# 04-OUTPUT.net
KiCad netlist of a schematic drawn in Altium Designer
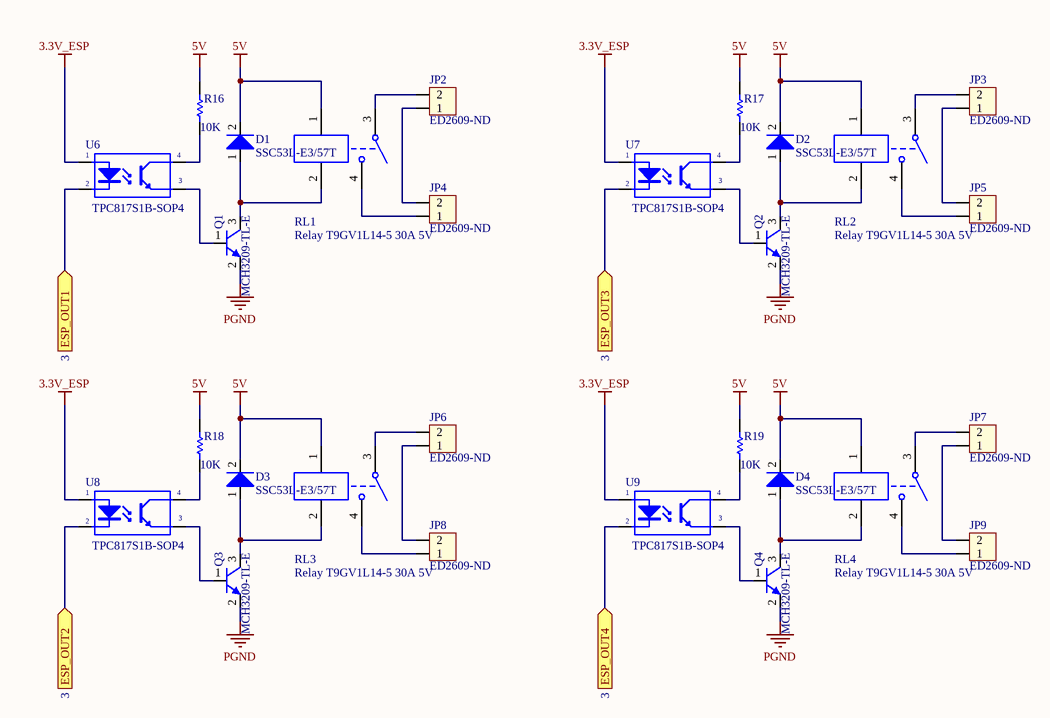
[diagram p0: 04-OUTPUT.SchDoc]

(export (version "E")
  (design (tool "Eeschema 10.0.6"))
  (components
    (comp (ref "D1")
      (value "SSC53L-E3/57T")
      (footprint "SSC53L-E3/57T")
      (description "DIODE SCHOTTKY 30V 5A DO214AB")
      (libsource (lib "lpson") (part "10A10"))
    )
    (comp (ref "D2")
      (value "SSC53L-E3/57T")
      (footprint "SSC53L-E3/57T")
      (description "DIODE SCHOTTKY 30V 5A DO214AB")
      (libsource (lib "lpson") (part "10A10"))
    )
    (comp (ref "D3")
      (value "SSC53L-E3/57T")
      (footprint "SSC53L-E3/57T")
      (description "DIODE SCHOTTKY 30V 5A DO214AB")
      (libsource (lib "lpson") (part "10A10"))
    )
    (comp (ref "D4")
      (value "SSC53L-E3/57T")
      (footprint "SSC53L-E3/57T")
      (description "DIODE SCHOTTKY 30V 5A DO214AB")
      (libsource (lib "lpson") (part "10A10"))
    )
    (comp (ref "JP2")
      (value "ED2609-ND")
      (footprint "DOMINO_OSTTC_2P")
      (description "2 Position Wire to Board Terminal Block Horizontal with Board 0.200\" (5.08mm) Through Hole")
      (libsource (lib "lpson") (part "Con2"))
    )
    (comp (ref "JP3")
      (value "ED2609-ND")
      (footprint "DOMINO_OSTTC_2P")
      (description "2 Position Wire to Board Terminal Block Horizontal with Board 0.200\" (5.08mm) Through Hole")
      (libsource (lib "lpson") (part "Con2"))
    )
    (comp (ref "JP4")
      (value "ED2609-ND")
      (footprint "DOMINO_OSTTC_2P")
      (description "2 Position Wire to Board Terminal Block Horizontal with Board 0.200\" (5.08mm) Through Hole")
      (libsource (lib "lpson") (part "Con2"))
    )
    (comp (ref "JP5")
      (value "ED2609-ND")
      (footprint "DOMINO_OSTTC_2P")
      (description "2 Position Wire to Board Terminal Block Horizontal with Board 0.200\" (5.08mm) Through Hole")
      (libsource (lib "lpson") (part "Con2"))
    )
    (comp (ref "JP6")
      (value "ED2609-ND")
      (footprint "DOMINO_OSTTC_2P")
      (description "2 Position Wire to Board Terminal Block Horizontal with Board 0.200\" (5.08mm) Through Hole")
      (libsource (lib "lpson") (part "Con2"))
    )
    (comp (ref "JP7")
      (value "ED2609-ND")
      (footprint "DOMINO_OSTTC_2P")
      (description "2 Position Wire to Board Terminal Block Horizontal with Board 0.200\" (5.08mm) Through Hole")
      (libsource (lib "lpson") (part "Con2"))
    )
    (comp (ref "JP8")
      (value "ED2609-ND")
      (footprint "DOMINO_OSTTC_2P")
      (description "2 Position Wire to Board Terminal Block Horizontal with Board 0.200\" (5.08mm) Through Hole")
      (libsource (lib "lpson") (part "Con2"))
    )
    (comp (ref "JP9")
      (value "ED2609-ND")
      (footprint "DOMINO_OSTTC_2P")
      (description "2 Position Wire to Board Terminal Block Horizontal with Board 0.200\" (5.08mm) Through Hole")
      (libsource (lib "lpson") (part "Con2"))
    )
    (comp (ref "Q1")
      (value "MCH3209-TL-E")
      (footprint "MCH3209-TL-E  SOT-323")
      (description "Bipolar (BJT) Transistor NPN 30V 3A 450MHz 800mW Surface Mount 3-MCPH")
      (libsource (lib "lpson") (part "2SC1815"))
    )
    (comp (ref "Q2")
      (value "MCH3209-TL-E")
      (footprint "MCH3209-TL-E  SOT-323")
      (description "Bipolar (BJT) Transistor NPN 30V 3A 450MHz 800mW Surface Mount 3-MCPH")
      (libsource (lib "lpson") (part "2SC1815"))
    )
    (comp (ref "Q3")
      (value "MCH3209-TL-E")
      (footprint "MCH3209-TL-E  SOT-323")
      (description "Bipolar (BJT) Transistor NPN 30V 3A 450MHz 800mW Surface Mount 3-MCPH")
      (libsource (lib "lpson") (part "2SC1815"))
    )
    (comp (ref "Q4")
      (value "MCH3209-TL-E")
      (footprint "MCH3209-TL-E  SOT-323")
      (description "Bipolar (BJT) Transistor NPN 30V 3A 450MHz 800mW Surface Mount 3-MCPH")
      (libsource (lib "lpson") (part "2SC1815"))
    )
    (comp (ref "R16")
      (value "10K")
      (footprint "Res 0805 SMD")
      (description "RES SMD 249K OHM 1% 1/10W 0805")
      (fields
        (field (name "MANUFACTURER") "Yageo")
        (field (name "MANUFACTURER PART NUMBER") "RC0603FR-07249KL")
      )
      (libsource (lib "GSHT_181013") (part "249K/R0805/1%"))
    )
    (comp (ref "R17")
      (value "10K")
      (footprint "Res 0805 SMD")
      (description "RES SMD 249K OHM 1% 1/10W 0805")
      (fields
        (field (name "MANUFACTURER") "Yageo")
        (field (name "MANUFACTURER PART NUMBER") "RC0603FR-07249KL")
      )
      (libsource (lib "GSHT_181013") (part "249K/R0805/1%"))
    )
    (comp (ref "R18")
      (value "10K")
      (footprint "Res 0805 SMD")
      (description "RES SMD 249K OHM 1% 1/10W 0805")
      (fields
        (field (name "MANUFACTURER") "Yageo")
        (field (name "MANUFACTURER PART NUMBER") "RC0603FR-07249KL")
      )
      (libsource (lib "GSHT_181013") (part "249K/R0805/1%"))
    )
    (comp (ref "R19")
      (value "10K")
      (footprint "Res 0805 SMD")
      (description "RES SMD 249K OHM 1% 1/10W 0805")
      (fields
        (field (name "MANUFACTURER") "Yageo")
        (field (name "MANUFACTURER PART NUMBER") "RC0603FR-07249KL")
      )
      (libsource (lib "GSHT_181013") (part "249K/R0805/1%"))
    )
    (comp (ref "RL1")
      (value "Relay T9GV1L14-5 30A 5V")
      (footprint "Relay T9GV1L14-5 30A 5V")
      (description "General Purpose Relay SPST-NO (1 Form A) 5VDC Coil Through Hole")
      (libsource (lib "PCB_ESP32_RFID") (part "Relay T9GV1L14-5 30A 5V"))
    )
    (comp (ref "RL2")
      (value "Relay T9GV1L14-5 30A 5V")
      (footprint "Relay T9GV1L14-5 30A 5V")
      (description "General Purpose Relay SPST-NO (1 Form A) 5VDC Coil Through Hole")
      (libsource (lib "PCB_ESP32_RFID") (part "Relay T9GV1L14-5 30A 5V"))
    )
    (comp (ref "RL3")
      (value "Relay T9GV1L14-5 30A 5V")
      (footprint "Relay T9GV1L14-5 30A 5V")
      (description "General Purpose Relay SPST-NO (1 Form A) 5VDC Coil Through Hole")
      (libsource (lib "PCB_ESP32_RFID") (part "Relay T9GV1L14-5 30A 5V"))
    )
    (comp (ref "RL4")
      (value "Relay T9GV1L14-5 30A 5V")
      (footprint "Relay T9GV1L14-5 30A 5V")
      (description "General Purpose Relay SPST-NO (1 Form A) 5VDC Coil Through Hole")
      (libsource (lib "PCB_ESP32_RFID") (part "Relay T9GV1L14-5 30A 5V"))
    )
    (comp (ref "U6")
      (value "TPC817S1B-SOP4")
      (footprint "TPC817-4SOP")
      (description "Optoisolator Transistor Output 5000Vrms 1 Channel 4-SOP")
      (libsource (lib "lpson") (part "PC817"))
    )
    (comp (ref "U7")
      (value "TPC817S1B-SOP4")
      (footprint "TPC817-4SOP")
      (description "Optoisolator Transistor Output 5000Vrms 1 Channel 4-SOP")
      (libsource (lib "lpson") (part "PC817"))
    )
    (comp (ref "U8")
      (value "TPC817S1B-SOP4")
      (footprint "TPC817-4SOP")
      (description "Optoisolator Transistor Output 5000Vrms 1 Channel 4-SOP")
      (libsource (lib "lpson") (part "PC817"))
    )
    (comp (ref "U9")
      (value "TPC817S1B-SOP4")
      (footprint "TPC817-4SOP")
      (description "Optoisolator Transistor Output 5000Vrms 1 Channel 4-SOP")
      (libsource (lib "lpson") (part "PC817"))
    )
  )
  (nets
    (net (code "1") (name "/ESP_OUT1") (class "Default")
      (node (ref "U6") (pin "2") (pinfunction "K_2") (pintype "passive"))
    )
    (net (code "2") (name "/ESP_OUT2") (class "Default")
      (node (ref "U8") (pin "2") (pinfunction "K_2") (pintype "passive"))
    )
    (net (code "3") (name "/ESP_OUT3") (class "Default")
      (node (ref "U7") (pin "2") (pinfunction "K_2") (pintype "passive"))
    )
    (net (code "4") (name "/ESP_OUT4") (class "Default")
      (node (ref "U9") (pin "2") (pinfunction "K_2") (pintype "passive"))
    )
    (net (code "5") (name "3.3V_ESP") (class "Default")
      (node (ref "U6") (pin "1") (pinfunction "A_1") (pintype "passive"))
      (node (ref "U7") (pin "1") (pinfunction "A_1") (pintype "passive"))
      (node (ref "U8") (pin "1") (pinfunction "A_1") (pintype "passive"))
      (node (ref "U9") (pin "1") (pinfunction "A_1") (pintype "passive"))
    )
    (net (code "6") (name "5V") (class "Default")
      (node (ref "D1") (pin "2") (pinfunction "K_2") (pintype "passive"))
      (node (ref "D2") (pin "2") (pinfunction "K_2") (pintype "passive"))
      (node (ref "D3") (pin "2") (pinfunction "K_2") (pintype "passive"))
      (node (ref "D4") (pin "2") (pinfunction "K_2") (pintype "passive"))
      (node (ref "R16") (pin "2") (pinfunction "2_2") (pintype "passive"))
      (node (ref "R17") (pin "2") (pinfunction "2_2") (pintype "passive"))
      (node (ref "R18") (pin "2") (pinfunction "2_2") (pintype "passive"))
      (node (ref "R19") (pin "2") (pinfunction "2_2") (pintype "passive"))
      (node (ref "RL1") (pin "1") (pinfunction "1_1") (pintype "passive"))
      (node (ref "RL2") (pin "1") (pinfunction "1_1") (pintype "passive"))
      (node (ref "RL3") (pin "1") (pinfunction "1_1") (pintype "passive"))
      (node (ref "RL4") (pin "1") (pinfunction "1_1") (pintype "passive"))
    )
    (net (code "7") (name "Net-(D1-A)") (class "Default")
      (node (ref "D1") (pin "1") (pinfunction "A_1") (pintype "passive"))
      (node (ref "Q1") (pin "3") (pinfunction "C_3") (pintype "passive"))
      (node (ref "RL1") (pin "2") (pinfunction "2_2") (pintype "passive"))
    )
    (net (code "8") (name "Net-(D2-A)") (class "Default")
      (node (ref "D2") (pin "1") (pinfunction "A_1") (pintype "passive"))
      (node (ref "Q2") (pin "3") (pinfunction "C_3") (pintype "passive"))
      (node (ref "RL2") (pin "2") (pinfunction "2_2") (pintype "passive"))
    )
    (net (code "9") (name "Net-(D3-A)") (class "Default")
      (node (ref "D3") (pin "1") (pinfunction "A_1") (pintype "passive"))
      (node (ref "Q3") (pin "3") (pinfunction "C_3") (pintype "passive"))
      (node (ref "RL3") (pin "2") (pinfunction "2_2") (pintype "passive"))
    )
    (net (code "10") (name "Net-(D4-A)") (class "Default")
      (node (ref "D4") (pin "1") (pinfunction "A_1") (pintype "passive"))
      (node (ref "Q4") (pin "3") (pinfunction "C_3") (pintype "passive"))
      (node (ref "RL4") (pin "2") (pinfunction "2_2") (pintype "passive"))
    )
    (net (code "11") (name "Net-(JP2-Pad1)") (class "Default")
      (node (ref "JP2") (pin "1") (pinfunction "1_1") (pintype "passive"))
      (node (ref "JP4") (pin "2") (pinfunction "2_2") (pintype "passive"))
    )
    (net (code "12") (name "Net-(JP2-Pad2)") (class "Default")
      (node (ref "JP2") (pin "2") (pinfunction "2_2") (pintype "passive"))
      (node (ref "RL1") (pin "3") (pinfunction "3_3") (pintype "passive"))
    )
    (net (code "13") (name "Net-(JP3-Pad1)") (class "Default")
      (node (ref "JP3") (pin "1") (pinfunction "1_1") (pintype "passive"))
      (node (ref "JP5") (pin "2") (pinfunction "2_2") (pintype "passive"))
    )
    (net (code "14") (name "Net-(JP3-Pad2)") (class "Default")
      (node (ref "JP3") (pin "2") (pinfunction "2_2") (pintype "passive"))
      (node (ref "RL2") (pin "3") (pinfunction "3_3") (pintype "passive"))
    )
    (net (code "15") (name "Net-(JP4-Pad1)") (class "Default")
      (node (ref "JP4") (pin "1") (pinfunction "1_1") (pintype "passive"))
      (node (ref "RL1") (pin "4") (pinfunction "4_4") (pintype "passive"))
    )
    (net (code "16") (name "Net-(JP5-Pad1)") (class "Default")
      (node (ref "JP5") (pin "1") (pinfunction "1_1") (pintype "passive"))
      (node (ref "RL2") (pin "4") (pinfunction "4_4") (pintype "passive"))
    )
    (net (code "17") (name "Net-(JP6-Pad1)") (class "Default")
      (node (ref "JP6") (pin "1") (pinfunction "1_1") (pintype "passive"))
      (node (ref "JP8") (pin "2") (pinfunction "2_2") (pintype "passive"))
    )
    (net (code "18") (name "Net-(JP6-Pad2)") (class "Default")
      (node (ref "JP6") (pin "2") (pinfunction "2_2") (pintype "passive"))
      (node (ref "RL3") (pin "3") (pinfunction "3_3") (pintype "passive"))
    )
    (net (code "19") (name "Net-(JP7-Pad1)") (class "Default")
      (node (ref "JP7") (pin "1") (pinfunction "1_1") (pintype "passive"))
      (node (ref "JP9") (pin "2") (pinfunction "2_2") (pintype "passive"))
    )
    (net (code "20") (name "Net-(JP7-Pad2)") (class "Default")
      (node (ref "JP7") (pin "2") (pinfunction "2_2") (pintype "passive"))
      (node (ref "RL4") (pin "3") (pinfunction "3_3") (pintype "passive"))
    )
    (net (code "21") (name "Net-(JP8-Pad1)") (class "Default")
      (node (ref "JP8") (pin "1") (pinfunction "1_1") (pintype "passive"))
      (node (ref "RL3") (pin "4") (pinfunction "4_4") (pintype "passive"))
    )
    (net (code "22") (name "Net-(JP9-Pad1)") (class "Default")
      (node (ref "JP9") (pin "1") (pinfunction "1_1") (pintype "passive"))
      (node (ref "RL4") (pin "4") (pinfunction "4_4") (pintype "passive"))
    )
    (net (code "23") (name "Net-(Q1-B)") (class "Default")
      (node (ref "Q1") (pin "1") (pinfunction "B_1") (pintype "passive"))
      (node (ref "U6") (pin "3") (pinfunction "E_3") (pintype "passive"))
    )
    (net (code "24") (name "Net-(Q2-B)") (class "Default")
      (node (ref "Q2") (pin "1") (pinfunction "B_1") (pintype "passive"))
      (node (ref "U7") (pin "3") (pinfunction "E_3") (pintype "passive"))
    )
    (net (code "25") (name "Net-(Q3-B)") (class "Default")
      (node (ref "Q3") (pin "1") (pinfunction "B_1") (pintype "passive"))
      (node (ref "U8") (pin "3") (pinfunction "E_3") (pintype "passive"))
    )
    (net (code "26") (name "Net-(Q4-B)") (class "Default")
      (node (ref "Q4") (pin "1") (pinfunction "B_1") (pintype "passive"))
      (node (ref "U9") (pin "3") (pinfunction "E_3") (pintype "passive"))
    )
    (net (code "27") (name "Net-(U6-C)") (class "Default")
      (node (ref "R16") (pin "1") (pinfunction "1_1") (pintype "passive"))
      (node (ref "U6") (pin "4") (pinfunction "C_4") (pintype "passive"))
    )
    (net (code "28") (name "Net-(U7-C)") (class "Default")
      (node (ref "R17") (pin "1") (pinfunction "1_1") (pintype "passive"))
      (node (ref "U7") (pin "4") (pinfunction "C_4") (pintype "passive"))
    )
    (net (code "29") (name "Net-(U8-C)") (class "Default")
      (node (ref "R18") (pin "1") (pinfunction "1_1") (pintype "passive"))
      (node (ref "U8") (pin "4") (pinfunction "C_4") (pintype "passive"))
    )
    (net (code "30") (name "Net-(U9-C)") (class "Default")
      (node (ref "R19") (pin "1") (pinfunction "1_1") (pintype "passive"))
      (node (ref "U9") (pin "4") (pinfunction "C_4") (pintype "passive"))
    )
    (net (code "31") (name "PGND") (class "Default")
      (node (ref "Q1") (pin "2") (pinfunction "E_2") (pintype "passive"))
      (node (ref "Q2") (pin "2") (pinfunction "E_2") (pintype "passive"))
      (node (ref "Q3") (pin "2") (pinfunction "E_2") (pintype "passive"))
      (node (ref "Q4") (pin "2") (pinfunction "E_2") (pintype "passive"))
    )
  )
)
